# SparkFun_IR_Receiver.net
KiCad netlist of a schematic drawn in EAGLE
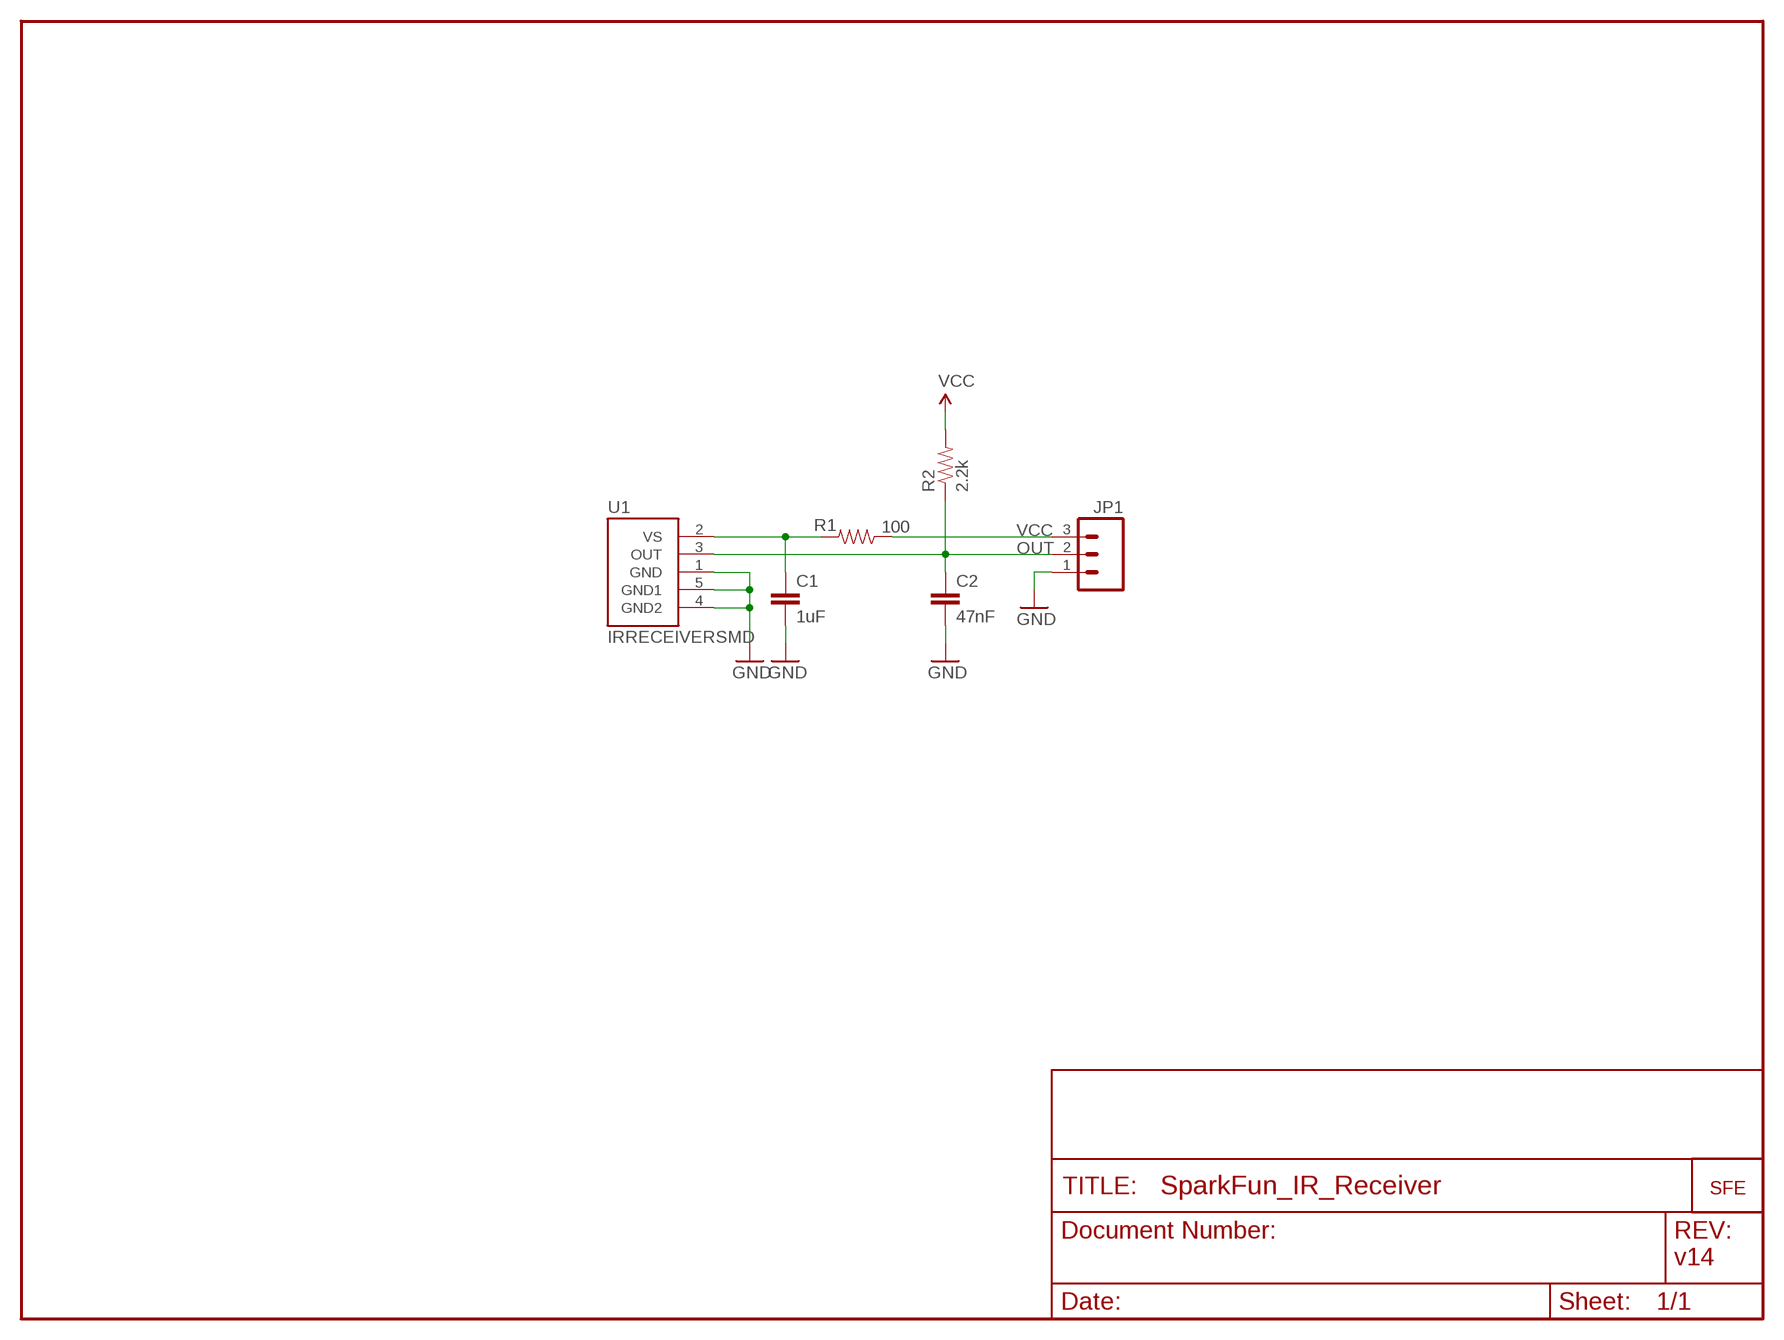
[diagram p0: schematic, sheet 1]

(export (version "E")
  (design (tool "Eeschema 10.0.6"))
  (components
    (comp (ref "C1")
      (value "1uF")
      (footprint "eagle-import:0603-CAP")
      (libsource (lib "eagle-import") (part "CAP0603-CAP"))
    )
    (comp (ref "C2")
      (value "47nF")
      (footprint "eagle-import:0603-CAP")
      (libsource (lib "eagle-import") (part "CAP0603-CAP"))
    )
    (comp (ref "JP1")
      (value "M03PTH")
      (footprint "eagle-import:1X03")
      (libsource (lib "eagle-import") (part "M03PTH"))
    )
    (comp (ref "R1")
      (value "100")
      (footprint "eagle-import:0603-RES")
      (libsource (lib "eagle-import") (part "RESISTOR0603-RES"))
    )
    (comp (ref "R2")
      (value "2.2k")
      (footprint "eagle-import:0603-RES")
      (libsource (lib "eagle-import") (part "RESISTOR0603-RES"))
    )
    (comp (ref "U$1")
      (value "LOGO-SFESK")
      (footprint "eagle-import:SFE-LOGO-FLAME")
      (libsource (lib "eagle-import") (part "LOGO-SFESK"))
    )
    (comp (ref "U1")
      (value "IRRECEIVERSMD")
      (footprint "eagle-import:TSOP8523")
      (libsource (lib "eagle-import") (part "IRRECEIVERSMD"))
    )
  )
  (nets
    (net (code "1") (name "/OUT") (class "Default")
      (node (ref "C2") (pin "1") (pinfunction "1_1") (pintype "passive"))
      (node (ref "JP1") (pin "2") (pinfunction "2_2") (pintype "passive"))
      (node (ref "R2") (pin "1") (pinfunction "1_1") (pintype "passive"))
      (node (ref "U1") (pin "3") (pinfunction "OUT_3") (pintype "bidirectional"))
    )
    (net (code "2") (name "GND") (class "Default")
      (node (ref "C1") (pin "2") (pinfunction "2_2") (pintype "passive"))
      (node (ref "C2") (pin "2") (pinfunction "2_2") (pintype "passive"))
      (node (ref "JP1") (pin "1") (pinfunction "1_1") (pintype "passive"))
      (node (ref "U1") (pin "1") (pinfunction "GND_1") (pintype "bidirectional"))
      (node (ref "U1") (pin "4") (pinfunction "GND2_4") (pintype "bidirectional"))
      (node (ref "U1") (pin "5") (pinfunction "GND1_5") (pintype "bidirectional"))
    )
    (net (code "3") (name "Net-(U1-VS)") (class "Default")
      (node (ref "C1") (pin "1") (pinfunction "1_1") (pintype "passive"))
      (node (ref "R1") (pin "2") (pinfunction "2_2") (pintype "passive"))
      (node (ref "U1") (pin "2") (pinfunction "VS_2") (pintype "bidirectional"))
    )
    (net (code "4") (name "VCC") (class "Default")
      (node (ref "JP1") (pin "3") (pinfunction "3_3") (pintype "passive"))
      (node (ref "R1") (pin "1") (pinfunction "1_1") (pintype "passive"))
      (node (ref "R2") (pin "2") (pinfunction "2_2") (pintype "passive"))
    )
  )
)
